# -Y_panel_FM_2U_Ver1_v1.net
KiCad netlist of a schematic drawn in EAGLE
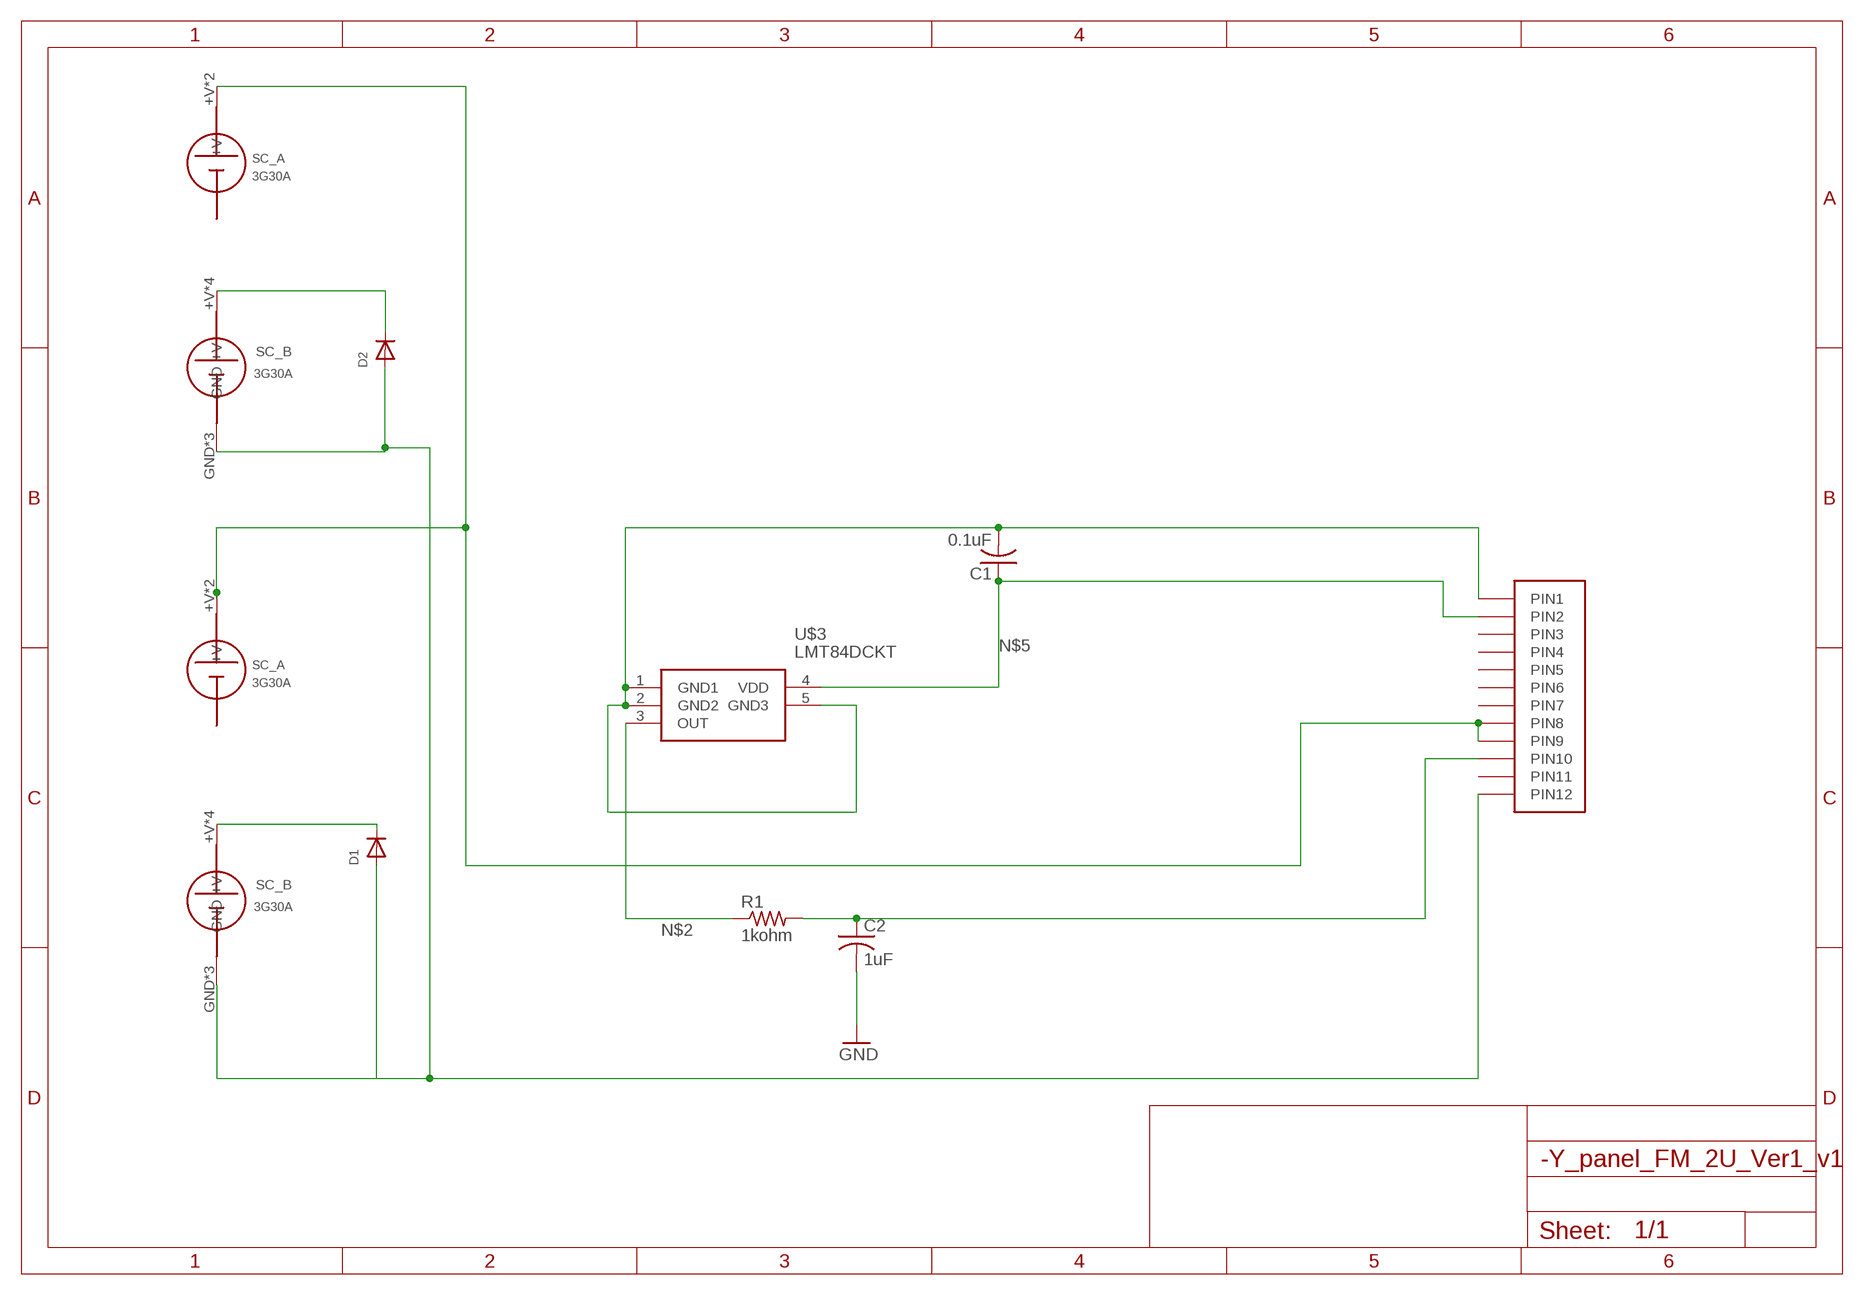
[diagram p0: schematic, sheet 1]

(export (version "E")
  (design (tool "Eeschema 10.0.6"))
  (components
    (comp (ref "C1")
      (value "0.1uF")
      (footprint "eagle-import:C0805")
      (libsource (lib "eagle-import") (part "C-USC0805"))
    )
    (comp (ref "C2")
      (value "1uF")
      (footprint "eagle-import:C0805")
      (libsource (lib "eagle-import") (part "C-USC0805"))
    )
    (comp (ref "D1")
      (value "DIODE_SOD-123FL")
      (footprint "eagle-import:SOD-123FL")
      (libsource (lib "eagle-import") (part "DIODE_SOD-123FL"))
    )
    (comp (ref "D2")
      (value "DIODE_SOD-123FL")
      (footprint "eagle-import:SOD-123FL")
      (libsource (lib "eagle-import") (part "DIODE_SOD-123FL"))
    )
    (comp (ref "R1")
      (value "1kohm")
      (footprint "eagle-import:R0402")
      (libsource (lib "eagle-import") (part "R-US_R0402"))
    )
    (comp (ref "SOLARCELL_A")
      (value "SC_A")
      (footprint "eagle-import:SC_A")
      (libsource (lib "eagle-import") (part "SC_A"))
    )
    (comp (ref "SOLARCELL_A1")
      (value "SC_A")
      (footprint "eagle-import:SC_A")
      (libsource (lib "eagle-import") (part "SC_A"))
    )
    (comp (ref "SOLARCELL_B")
      (value "SC_B")
      (footprint "eagle-import:SC_B")
      (libsource (lib "eagle-import") (part "SC_B"))
    )
    (comp (ref "SOLARCELL_B1")
      (value "SC_B")
      (footprint "eagle-import:SC_B")
      (fields (field (name "SPICEPREFIX") "B"))
      (libsource (lib "eagle-import") (part "SC_B"))
    )
    (comp (ref "U$1")
      (value "HEADER12PIN")
      (footprint "eagle-import:HEADER12PIN")
      (libsource (lib "eagle-import") (part "HEADER12PIN"))
    )
    (comp (ref "U$3")
      (value "LMT84DCKT")
      (footprint "eagle-import:SOT65P210X110-5N")
      (fields (field (name "RS_PART_NUMBER") "8115860"))
      (libsource (lib "eagle-import") (part "LMT84DCKT"))
    )
  )
  (nets
    (net (code "1") (name "/N$2") (class "Default")
      (node (ref "R1") (pin "1") (pinfunction "1_1") (pintype "passive"))
      (node (ref "U$3") (pin "3") (pinfunction "OUT_3") (pintype "output"))
    )
    (net (code "2") (name "/N$5") (class "Default")
      (node (ref "C1") (pin "1") (pinfunction "1_1") (pintype "passive"))
      (node (ref "U$1") (pin "P2") (pinfunction "PIN2_P2") (pintype "bidirectional"))
      (node (ref "U$3") (pin "4") (pinfunction "VDD_4") (pintype "power_in"))
    )
    (net (code "3") (name "GND") (class "Default")
      (node (ref "C1") (pin "2") (pinfunction "2_2") (pintype "passive"))
      (node (ref "C2") (pin "2") (pinfunction "2_2") (pintype "passive"))
      (node (ref "D1") (pin "A") (pinfunction "A_A") (pintype "passive"))
      (node (ref "D2") (pin "A") (pinfunction "A_A") (pintype "passive"))
      (node (ref "SOLARCELL_B") (pin "GND") (pinfunction "GND_GND") (pintype "bidirectional"))
      (node (ref "SOLARCELL_B") (pin "GND1") (pinfunction "GND_GND1") (pintype "bidirectional"))
      (node (ref "SOLARCELL_B") (pin "GND2") (pinfunction "GND_GND2") (pintype "bidirectional"))
      (node (ref "SOLARCELL_B1") (pin "GND") (pinfunction "GND_GND") (pintype "bidirectional"))
      (node (ref "SOLARCELL_B1") (pin "GND1") (pinfunction "GND_GND1") (pintype "bidirectional"))
      (node (ref "SOLARCELL_B1") (pin "GND2") (pinfunction "GND_GND2") (pintype "bidirectional"))
      (node (ref "U$1") (pin "P1") (pinfunction "PIN1_P1") (pintype "bidirectional"))
      (node (ref "U$1") (pin "P12") (pinfunction "PIN12_P12") (pintype "bidirectional"))
      (node (ref "U$3") (pin "1") (pinfunction "GND1_1") (pintype "power_in"))
      (node (ref "U$3") (pin "2") (pinfunction "GND2_2") (pintype "power_in"))
      (node (ref "U$3") (pin "5") (pinfunction "GND3_5") (pintype "power_in"))
    )
    (net (code "4") (name "Net-(D1-PadC)") (class "Default")
      (node (ref "D1") (pin "C") (pinfunction "C_C") (pintype "passive"))
      (node (ref "SOLARCELL_B") (pin "+V") (pinfunction "+V_+V") (pintype "bidirectional"))
      (node (ref "SOLARCELL_B") (pin "+V2") (pinfunction "+V_+V2") (pintype "bidirectional"))
      (node (ref "SOLARCELL_B") (pin "+V3") (pinfunction "+V_+V3") (pintype "bidirectional"))
      (node (ref "SOLARCELL_B") (pin "+V4") (pinfunction "+V_+V4") (pintype "bidirectional"))
    )
    (net (code "5") (name "Net-(D2-PadC)") (class "Default")
      (node (ref "D2") (pin "C") (pinfunction "C_C") (pintype "passive"))
      (node (ref "SOLARCELL_B1") (pin "+V") (pinfunction "+V_+V") (pintype "bidirectional"))
      (node (ref "SOLARCELL_B1") (pin "+V2") (pinfunction "+V_+V2") (pintype "bidirectional"))
      (node (ref "SOLARCELL_B1") (pin "+V3") (pinfunction "+V_+V3") (pintype "bidirectional"))
      (node (ref "SOLARCELL_B1") (pin "+V4") (pinfunction "+V_+V4") (pintype "bidirectional"))
    )
    (net (code "6") (name "Net-(U$1-PIN8)") (class "Default")
      (node (ref "SOLARCELL_A") (pin "+V") (pinfunction "+V_+V") (pintype "bidirectional"))
      (node (ref "SOLARCELL_A") (pin "+V1") (pinfunction "+V_+V1") (pintype "bidirectional"))
      (node (ref "SOLARCELL_A1") (pin "+V") (pinfunction "+V_+V") (pintype "bidirectional"))
      (node (ref "SOLARCELL_A1") (pin "+V1") (pinfunction "+V_+V1") (pintype "bidirectional"))
      (node (ref "U$1") (pin "P8") (pinfunction "PIN8_P8") (pintype "bidirectional"))
      (node (ref "U$1") (pin "P9") (pinfunction "PIN9_P9") (pintype "bidirectional"))
    )
    (net (code "7") (name "Net-(U$1-PIN10)") (class "Default")
      (node (ref "C2") (pin "1") (pinfunction "1_1") (pintype "passive"))
      (node (ref "R1") (pin "2") (pinfunction "2_2") (pintype "passive"))
      (node (ref "U$1") (pin "P10") (pinfunction "PIN10_P10") (pintype "bidirectional"))
    )
    (net (code "8") (name "unconnected-(U$1-PIN3-PadP3)") (class "Default")
      (node (ref "U$1") (pin "P3") (pinfunction "PIN3_P3") (pintype "bidirectional"))
    )
    (net (code "9") (name "unconnected-(U$1-PIN4-PadP4)") (class "Default")
      (node (ref "U$1") (pin "P4") (pinfunction "PIN4_P4") (pintype "bidirectional"))
    )
    (net (code "10") (name "unconnected-(U$1-PIN5-PadP5)") (class "Default")
      (node (ref "U$1") (pin "P5") (pinfunction "PIN5_P5") (pintype "bidirectional"))
    )
    (net (code "11") (name "unconnected-(U$1-PIN6-PadP6)") (class "Default")
      (node (ref "U$1") (pin "P6") (pinfunction "PIN6_P6") (pintype "bidirectional"))
    )
    (net (code "12") (name "unconnected-(U$1-PIN7-PadP7)") (class "Default")
      (node (ref "U$1") (pin "P7") (pinfunction "PIN7_P7") (pintype "bidirectional"))
    )
    (net (code "13") (name "unconnected-(U$1-PIN11-PadP11)") (class "Default")
      (node (ref "U$1") (pin "P11") (pinfunction "PIN11_P11") (pintype "bidirectional"))
    )
  )
)
